# correli_V1.net
KiCad netlist of a schematic drawn in EAGLE
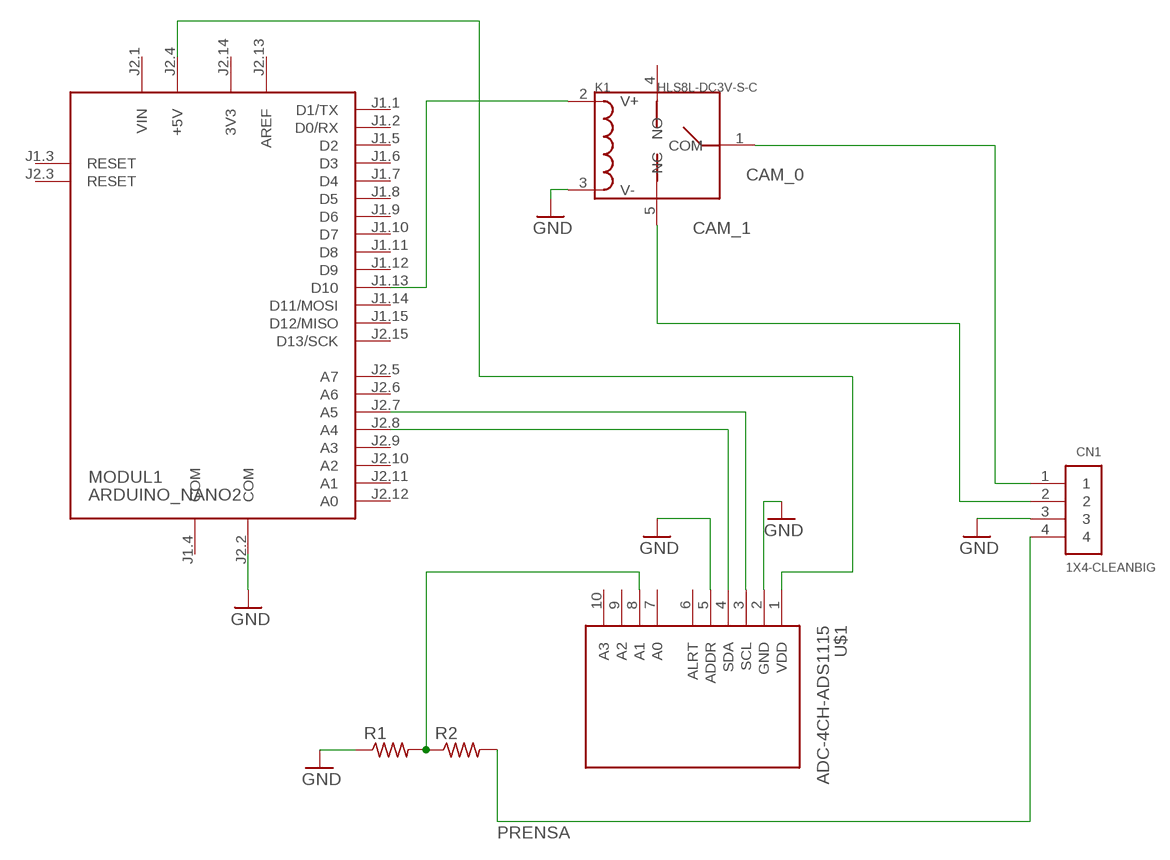
[diagram p0: schematic, sheet 1]

(export (version "E")
  (design (tool "Eeschema 10.0.6"))
  (components
    (comp (ref "CN1")
      (value "1X4-CLEANBIG")
      (footprint "eagle-import:1X04-CLEANBIG")
      (libsource (lib "eagle-import") (part "1X4-CLEANBIG"))
    )
    (comp (ref "K1")
      (value "HLS8L-DC3V-S-C")
      (footprint "eagle-import:REY5-19.0X15.0X15.0MM")
      (libsource (lib "eagle-import") (part "RELAY-HLS8L-DC3V-S-C(5P-19X15MM)"))
    )
    (comp (ref "MODUL1")
      (value "ARDUINO_NANO2")
      (footprint "eagle-import:ARDUINO_NANO2")
      (libsource (lib "eagle-import") (part "ARDUINO_NANO2"))
    )
    (comp (ref "R1")
      (value "R-US_0309/12")
      (footprint "eagle-import:0309_12")
      (libsource (lib "eagle-import") (part "R-US_0309/12"))
    )
    (comp (ref "R2")
      (value "R-US_0309/12")
      (footprint "eagle-import:0309_12")
      (libsource (lib "eagle-import") (part "R-US_0309/12"))
    )
    (comp (ref "U$1")
      (value "ADC-4CH-ADS1115")
      (footprint "eagle-import:ADC-4CH-ADS1115")
      (libsource (lib "eagle-import") (part "ADC-4CH-ADS1115"))
    )
  )
  (nets
    (net (code "1") (name "/3V3") (class "Default")
      (node (ref "MODUL1") (pin "J2.14") (pinfunction "3V3_J2.14") (pintype "power_in"))
    )
    (net (code "2") (name "/AREF") (class "Default")
      (node (ref "MODUL1") (pin "J2.13") (pinfunction "AREF_J2.13") (pintype "power_in"))
    )
    (net (code "3") (name "/CAM_0") (class "Default")
      (node (ref "CN1") (pin "1") (pinfunction "1_1") (pintype "bidirectional"))
      (node (ref "K1") (pin "1") (pinfunction "COM_1") (pintype "bidirectional"))
    )
    (net (code "4") (name "/CAM_1") (class "Default")
      (node (ref "CN1") (pin "2") (pinfunction "2_2") (pintype "bidirectional"))
      (node (ref "K1") (pin "5") (pinfunction "NC_5") (pintype "bidirectional"))
    )
    (net (code "5") (name "/COM") (class "Default")
      (node (ref "MODUL1") (pin "J1.4") (pinfunction "COM_J1.4") (pintype "power_in"))
    )
    (net (code "6") (name "/PRENSA") (class "Default")
      (node (ref "CN1") (pin "4") (pinfunction "4_4") (pintype "bidirectional"))
      (node (ref "R2") (pin "2") (pinfunction "2_2") (pintype "passive"))
    )
    (net (code "7") (name "/VIN") (class "Default")
      (node (ref "MODUL1") (pin "J2.1") (pinfunction "VIN_J2.1") (pintype "power_in"))
    )
    (net (code "8") (name "GND") (class "Default")
      (node (ref "CN1") (pin "3") (pinfunction "3_3") (pintype "bidirectional"))
      (node (ref "K1") (pin "3") (pinfunction "V-_3") (pintype "bidirectional"))
      (node (ref "MODUL1") (pin "J2.2") (pinfunction "COM_J2.2") (pintype "power_in"))
      (node (ref "R1") (pin "1") (pinfunction "1_1") (pintype "passive"))
      (node (ref "U$1") (pin "2") (pinfunction "GND_2") (pintype "power_in"))
      (node (ref "U$1") (pin "5") (pinfunction "ADDR_5") (pintype "bidirectional"))
    )
    (net (code "9") (name "Net-(K1-V+)") (class "Default")
      (node (ref "K1") (pin "2") (pinfunction "V+_2") (pintype "bidirectional"))
      (node (ref "MODUL1") (pin "J1.13") (pinfunction "D10_J1.13") (pintype "bidirectional"))
    )
    (net (code "10") (name "Net-(MODUL1-+5V)") (class "Default")
      (node (ref "MODUL1") (pin "J2.4") (pinfunction "+5V_J2.4") (pintype "power_in"))
      (node (ref "U$1") (pin "1") (pinfunction "VDD_1") (pintype "power_in"))
    )
    (net (code "11") (name "Net-(MODUL1-A4)") (class "Default")
      (node (ref "MODUL1") (pin "J2.8") (pinfunction "A4_J2.8") (pintype "bidirectional"))
      (node (ref "U$1") (pin "4") (pinfunction "SDA_4") (pintype "bidirectional"))
    )
    (net (code "12") (name "Net-(MODUL1-A5)") (class "Default")
      (node (ref "MODUL1") (pin "J2.7") (pinfunction "A5_J2.7") (pintype "bidirectional"))
      (node (ref "U$1") (pin "3") (pinfunction "SCL_3") (pintype "bidirectional"))
    )
    (net (code "13") (name "Net-(U$1-A1)") (class "Default")
      (node (ref "R1") (pin "2") (pinfunction "2_2") (pintype "passive"))
      (node (ref "R2") (pin "1") (pinfunction "1_1") (pintype "passive"))
      (node (ref "U$1") (pin "8") (pinfunction "A1_8") (pintype "input"))
    )
    (net (code "14") (name "unconnected-(K1-NO-Pad4)") (class "Default")
      (node (ref "K1") (pin "4") (pinfunction "NO_4") (pintype "bidirectional"))
    )
    (net (code "15") (name "unconnected-(MODUL1-A0-PadJ2.12)") (class "Default")
      (node (ref "MODUL1") (pin "J2.12") (pinfunction "A0_J2.12") (pintype "bidirectional"))
    )
    (net (code "16") (name "unconnected-(MODUL1-A1-PadJ2.11)") (class "Default")
      (node (ref "MODUL1") (pin "J2.11") (pinfunction "A1_J2.11") (pintype "bidirectional"))
    )
    (net (code "17") (name "unconnected-(MODUL1-A2-PadJ2.10)") (class "Default")
      (node (ref "MODUL1") (pin "J2.10") (pinfunction "A2_J2.10") (pintype "bidirectional"))
    )
    (net (code "18") (name "unconnected-(MODUL1-A3-PadJ2.9)") (class "Default")
      (node (ref "MODUL1") (pin "J2.9") (pinfunction "A3_J2.9") (pintype "bidirectional"))
    )
    (net (code "19") (name "unconnected-(MODUL1-A6-PadJ2.6)") (class "Default")
      (node (ref "MODUL1") (pin "J2.6") (pinfunction "A6_J2.6") (pintype "bidirectional"))
    )
    (net (code "20") (name "unconnected-(MODUL1-A7-PadJ2.5)") (class "Default")
      (node (ref "MODUL1") (pin "J2.5") (pinfunction "A7_J2.5") (pintype "bidirectional"))
    )
    (net (code "21") (name "unconnected-(MODUL1-D0{slash}RX-PadJ1.2)") (class "Default")
      (node (ref "MODUL1") (pin "J1.2") (pinfunction "D0/RX_J1.2") (pintype "bidirectional"))
    )
    (net (code "22") (name "unconnected-(MODUL1-D1{slash}TX-PadJ1.1)") (class "Default")
      (node (ref "MODUL1") (pin "J1.1") (pinfunction "D1/TX_J1.1") (pintype "bidirectional"))
    )
    (net (code "23") (name "unconnected-(MODUL1-D2-PadJ1.5)") (class "Default")
      (node (ref "MODUL1") (pin "J1.5") (pinfunction "D2_J1.5") (pintype "bidirectional"))
    )
    (net (code "24") (name "unconnected-(MODUL1-D3-PadJ1.6)") (class "Default")
      (node (ref "MODUL1") (pin "J1.6") (pinfunction "D3_J1.6") (pintype "bidirectional"))
    )
    (net (code "25") (name "unconnected-(MODUL1-D4-PadJ1.7)") (class "Default")
      (node (ref "MODUL1") (pin "J1.7") (pinfunction "D4_J1.7") (pintype "bidirectional"))
    )
    (net (code "26") (name "unconnected-(MODUL1-D5-PadJ1.8)") (class "Default")
      (node (ref "MODUL1") (pin "J1.8") (pinfunction "D5_J1.8") (pintype "bidirectional"))
    )
    (net (code "27") (name "unconnected-(MODUL1-D6-PadJ1.9)") (class "Default")
      (node (ref "MODUL1") (pin "J1.9") (pinfunction "D6_J1.9") (pintype "bidirectional"))
    )
    (net (code "28") (name "unconnected-(MODUL1-D7-PadJ1.10)") (class "Default")
      (node (ref "MODUL1") (pin "J1.10") (pinfunction "D7_J1.10") (pintype "bidirectional"))
    )
    (net (code "29") (name "unconnected-(MODUL1-D8-PadJ1.11)") (class "Default")
      (node (ref "MODUL1") (pin "J1.11") (pinfunction "D8_J1.11") (pintype "bidirectional"))
    )
    (net (code "30") (name "unconnected-(MODUL1-D9-PadJ1.12)") (class "Default")
      (node (ref "MODUL1") (pin "J1.12") (pinfunction "D9_J1.12") (pintype "bidirectional"))
    )
    (net (code "31") (name "unconnected-(MODUL1-D11{slash}MOSI-PadJ1.14)") (class "Default")
      (node (ref "MODUL1") (pin "J1.14") (pinfunction "D11/MOSI_J1.14") (pintype "bidirectional"))
    )
    (net (code "32") (name "unconnected-(MODUL1-D12{slash}MISO-PadJ1.15)") (class "Default")
      (node (ref "MODUL1") (pin "J1.15") (pinfunction "D12/MISO_J1.15") (pintype "bidirectional"))
    )
    (net (code "33") (name "unconnected-(MODUL1-D13{slash}SCK-PadJ2.15)") (class "Default")
      (node (ref "MODUL1") (pin "J2.15") (pinfunction "D13/SCK_J2.15") (pintype "bidirectional"))
    )
    (net (code "34") (name "unconnected-(MODUL1-RESET-PadJ1.3)") (class "Default")
      (node (ref "MODUL1") (pin "J1.3") (pinfunction "RESET_J1.3") (pintype "bidirectional"))
    )
    (net (code "35") (name "unconnected-(MODUL1-RESET-PadJ2.3)") (class "Default")
      (node (ref "MODUL1") (pin "J2.3") (pinfunction "RESET_J2.3") (pintype "bidirectional"))
    )
    (net (code "36") (name "unconnected-(U$1-A0-Pad7)") (class "Default")
      (node (ref "U$1") (pin "7") (pinfunction "A0_7") (pintype "input"))
    )
    (net (code "37") (name "unconnected-(U$1-A2-Pad9)") (class "Default")
      (node (ref "U$1") (pin "9") (pinfunction "A2_9") (pintype "input"))
    )
    (net (code "38") (name "unconnected-(U$1-A3-Pad10)") (class "Default")
      (node (ref "U$1") (pin "10") (pinfunction "A3_10") (pintype "input"))
    )
    (net (code "39") (name "unconnected-(U$1-ALRT-Pad6)") (class "Default")
      (node (ref "U$1") (pin "6") (pinfunction "ALRT_6") (pintype "bidirectional"))
    )
  )
)
